# konektor_1.net
KiCad netlist of a schematic drawn in EAGLE
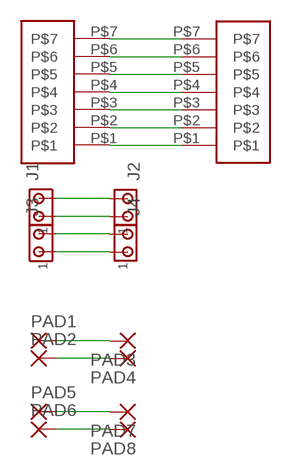
[diagram p0: schematic, sheet 1]

(export (version "E")
  (design (tool "Eeschema 10.0.6"))
  (components
    (comp (ref "J1")
      (value "MTA02-100")
      (footprint "eagle-import:10X02MTA")
      (libsource (lib "eagle-import") (part "MTA02-100"))
    )
    (comp (ref "J2")
      (value "MTA02-100")
      (footprint "eagle-import:10X02MTA")
      (libsource (lib "eagle-import") (part "MTA02-100"))
    )
    (comp (ref "J3")
      (value "MTA02-100")
      (footprint "eagle-import:10X02MTA")
      (libsource (lib "eagle-import") (part "MTA02-100"))
    )
    (comp (ref "J4")
      (value "MTA02-100")
      (footprint "eagle-import:10X02MTA")
      (libsource (lib "eagle-import") (part "MTA02-100"))
    )
    (comp (ref "PAD1")
      (value "2,54/0,8")
      (footprint "eagle-import:2,54_0,8")
      (libsource (lib "eagle-import") (part "2,54/0,8"))
    )
    (comp (ref "PAD2")
      (value "2,54/0,8")
      (footprint "eagle-import:2,54_0,8")
      (libsource (lib "eagle-import") (part "2,54/0,8"))
    )
    (comp (ref "PAD3")
      (value "2,54/0,8")
      (footprint "eagle-import:2,54_0,8")
      (libsource (lib "eagle-import") (part "2,54/0,8"))
    )
    (comp (ref "PAD4")
      (value "2,54/0,8")
      (footprint "eagle-import:2,54_0,8")
      (libsource (lib "eagle-import") (part "2,54/0,8"))
    )
    (comp (ref "PAD5")
      (value "2,54/0,8")
      (footprint "eagle-import:2,54_0,8")
      (libsource (lib "eagle-import") (part "2,54/0,8"))
    )
    (comp (ref "PAD6")
      (value "2,54/0,8")
      (footprint "eagle-import:2,54_0,8")
      (libsource (lib "eagle-import") (part "2,54/0,8"))
    )
    (comp (ref "PAD7")
      (value "2,54/0,8")
      (footprint "eagle-import:2,54_0,8")
      (libsource (lib "eagle-import") (part "2,54/0,8"))
    )
    (comp (ref "PAD8")
      (value "2,54/0,8")
      (footprint "eagle-import:2,54_0,8")
      (libsource (lib "eagle-import") (part "2,54/0,8"))
    )
    (comp (ref "U$1")
      (value "7PIN")
      (footprint "eagle-import:7PIN")
      (libsource (lib "eagle-import") (part "7PIN"))
    )
    (comp (ref "U$2")
      (value "7PIN")
      (footprint "eagle-import:7PIN")
      (libsource (lib "eagle-import") (part "7PIN"))
    )
  )
  (nets
    (net (code "1") (name "Net-(J1-Pad1)") (class "Default")
      (node (ref "J1") (pin "1") (pinfunction "1_1") (pintype "passive"))
      (node (ref "J2") (pin "1") (pinfunction "1_1") (pintype "passive"))
    )
    (net (code "2") (name "Net-(J1-Pad2)") (class "Default")
      (node (ref "J1") (pin "2") (pinfunction "2_2") (pintype "passive"))
      (node (ref "J2") (pin "2") (pinfunction "2_2") (pintype "passive"))
    )
    (net (code "3") (name "Net-(J3-Pad1)") (class "Default")
      (node (ref "J3") (pin "1") (pinfunction "1_1") (pintype "passive"))
      (node (ref "J4") (pin "1") (pinfunction "1_1") (pintype "passive"))
    )
    (net (code "4") (name "Net-(J3-Pad2)") (class "Default")
      (node (ref "J3") (pin "2") (pinfunction "2_2") (pintype "passive"))
      (node (ref "J4") (pin "2") (pinfunction "2_2") (pintype "passive"))
    )
    (net (code "5") (name "Net-(PAD1-P)") (class "Default")
      (node (ref "PAD1") (pin "1") (pinfunction "P_1") (pintype "passive"))
      (node (ref "PAD3") (pin "1") (pinfunction "P_1") (pintype "passive"))
    )
    (net (code "6") (name "Net-(PAD2-P)") (class "Default")
      (node (ref "PAD2") (pin "1") (pinfunction "P_1") (pintype "passive"))
      (node (ref "PAD4") (pin "1") (pinfunction "P_1") (pintype "passive"))
    )
    (net (code "7") (name "Net-(PAD5-P)") (class "Default")
      (node (ref "PAD5") (pin "1") (pinfunction "P_1") (pintype "passive"))
      (node (ref "PAD7") (pin "1") (pinfunction "P_1") (pintype "passive"))
    )
    (net (code "8") (name "Net-(PAD6-P)") (class "Default")
      (node (ref "PAD6") (pin "1") (pinfunction "P_1") (pintype "passive"))
      (node (ref "PAD8") (pin "1") (pinfunction "P_1") (pintype "passive"))
    )
    (net (code "9") (name "Net-(U$1-PadP$1)") (class "Default")
      (node (ref "U$1") (pin "P$1") (pinfunction "P$1_P$1") (pintype "bidirectional"))
      (node (ref "U$2") (pin "P$1") (pinfunction "P$1_P$1") (pintype "bidirectional"))
    )
    (net (code "10") (name "Net-(U$1-PadP$2)") (class "Default")
      (node (ref "U$1") (pin "P$2") (pinfunction "P$2_P$2") (pintype "bidirectional"))
      (node (ref "U$2") (pin "P$2") (pinfunction "P$2_P$2") (pintype "bidirectional"))
    )
    (net (code "11") (name "Net-(U$1-PadP$3)") (class "Default")
      (node (ref "U$1") (pin "P$3") (pinfunction "P$3_P$3") (pintype "bidirectional"))
      (node (ref "U$2") (pin "P$3") (pinfunction "P$3_P$3") (pintype "bidirectional"))
    )
    (net (code "12") (name "Net-(U$1-PadP$4)") (class "Default")
      (node (ref "U$1") (pin "P$4") (pinfunction "P$4_P$4") (pintype "bidirectional"))
      (node (ref "U$2") (pin "P$4") (pinfunction "P$4_P$4") (pintype "bidirectional"))
    )
    (net (code "13") (name "Net-(U$1-PadP$5)") (class "Default")
      (node (ref "U$1") (pin "P$5") (pinfunction "P$5_P$5") (pintype "bidirectional"))
      (node (ref "U$2") (pin "P$5") (pinfunction "P$5_P$5") (pintype "bidirectional"))
    )
    (net (code "14") (name "Net-(U$1-PadP$6)") (class "Default")
      (node (ref "U$1") (pin "P$6") (pinfunction "P$6_P$6") (pintype "bidirectional"))
      (node (ref "U$2") (pin "P$6") (pinfunction "P$6_P$6") (pintype "bidirectional"))
    )
    (net (code "15") (name "Net-(U$1-PadP$7)") (class "Default")
      (node (ref "U$1") (pin "P$7") (pinfunction "P$7_P$7") (pintype "bidirectional"))
      (node (ref "U$2") (pin "P$7") (pinfunction "P$7_P$7") (pintype "bidirectional"))
    )
  )
)
